# Version2.net
KiCad netlist of a schematic drawn in EasyEDA Pro
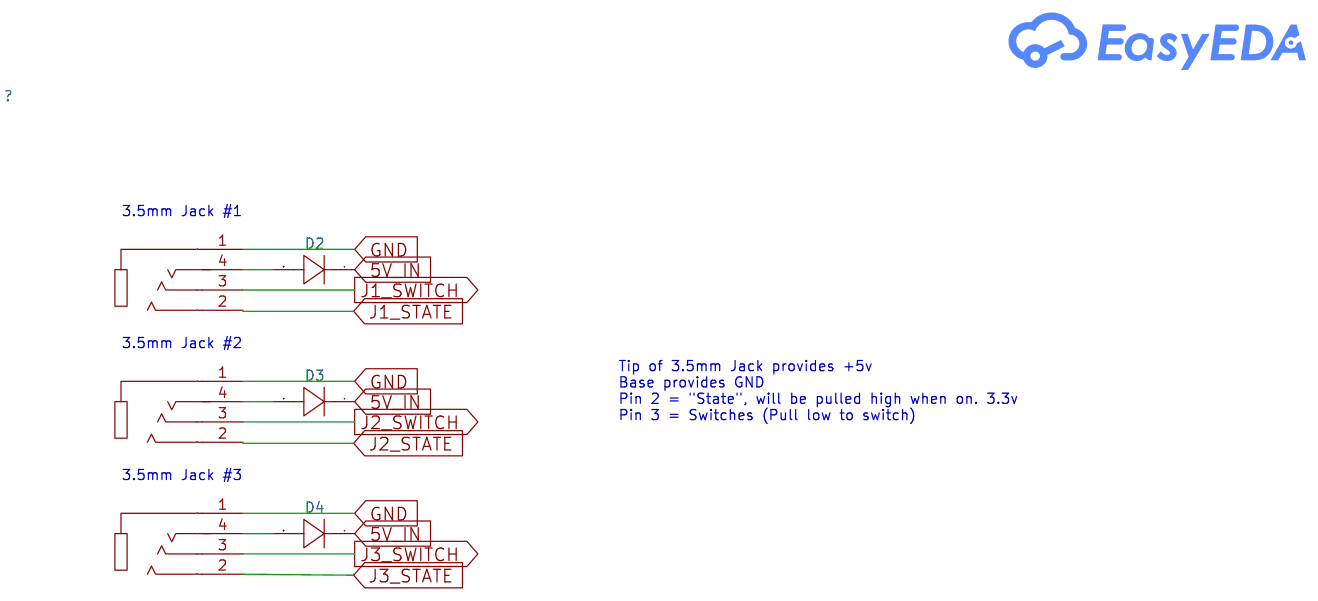
[diagram p0: inputs]
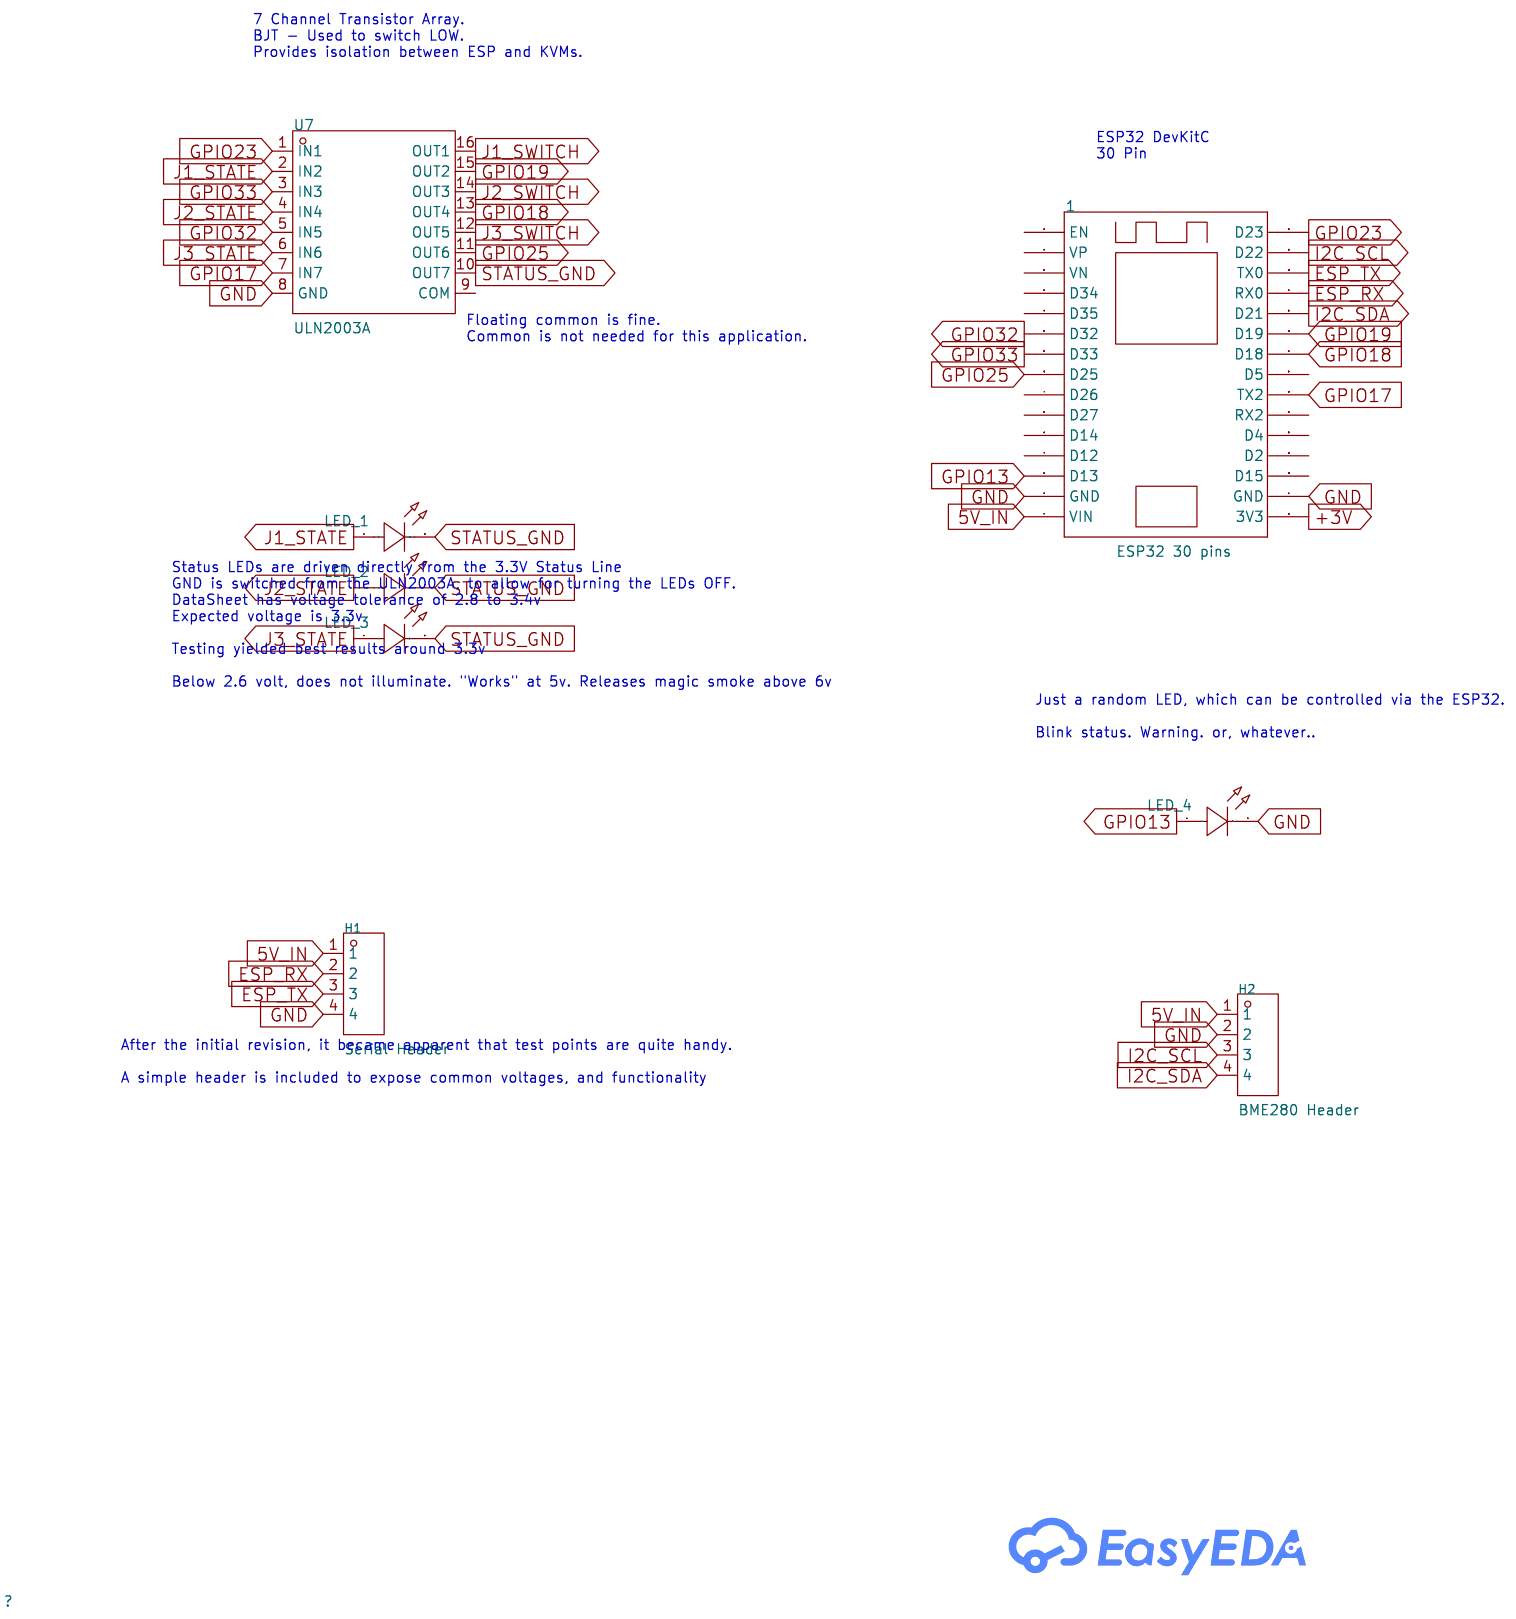
[diagram p1: logic]

(export (version "E")
  (design (tool "Eeschema 10.0.6"))
  (components
    (comp (ref "3.5mm1")
      (value "PJ-320D")
      (footprint "easyedapro:AUDIO-SMD_PJ-320D")
      (fields (field (name "Manufacturer") "SHOU HAN(首韩)"))
      (libsource (lib "easyedapro") (part "PJ-320D"))
    )
    (comp (ref "3.5mm2")
      (value "PJ-320D")
      (footprint "easyedapro:AUDIO-SMD_PJ-320D")
      (fields (field (name "Manufacturer") "SHOU HAN(首韩)"))
      (libsource (lib "easyedapro") (part "PJ-320D"))
    )
    (comp (ref "3.5mm3")
      (value "PJ-320D")
      (footprint "easyedapro:AUDIO-SMD_PJ-320D")
      (fields (field (name "Manufacturer") "SHOU HAN(首韩)"))
      (libsource (lib "easyedapro") (part "PJ-320D"))
    )
    (comp (ref "D2")
      (value "~")
      (footprint "easyedapro:DO-41_BD2.4-L4.7-P8.70-D0.9-RD")
      (libsource (lib "easyedapro") (part "D_1N4007"))
    )
    (comp (ref "D3")
      (value "~")
      (footprint "easyedapro:DO-41_BD2.4-L4.7-P8.70-D0.9-RD")
      (libsource (lib "easyedapro") (part "D_1N4007"))
    )
    (comp (ref "D4")
      (value "~")
      (footprint "easyedapro:DO-41_BD2.4-L4.7-P8.70-D0.9-RD")
      (libsource (lib "easyedapro") (part "D_1N4007"))
    )
    (comp (ref "1") (value "ESP32 30 pins") (libsource (lib "easyedapro") (part "ESP32 30 pins")))
    (comp (ref "H1")
      (value "Serial Header")
      (footprint "easyedapro:HDR-TH_4P-P2.54-V-M")
      (fields (field (name "Manufacturer") "XFCN(兴飞)"))
      (libsource (lib "easyedapro") (part "PZ254V-11-04P_C2691448"))
    )
    (comp (ref "H2")
      (value "BME280 Header")
      (footprint "easyedapro:HDR-TH_4P-P2.54-V-M")
      (fields (field (name "Manufacturer") "XFCN(兴飞)"))
      (libsource (lib "easyedapro") (part "PZ254V-11-04P_C2691448"))
    )
    (comp (ref "LED_1")
      (value "DY-332SUGD-A3")
      (footprint "easyedapro:LED-TH_BD5.9-P2.54-FD")
      (fields (field (name "Manufacturer") "TONYU(东裕)"))
      (libsource (lib "easyedapro") (part "DY-332SUGD-A3"))
    )
    (comp (ref "LED_2")
      (value "DY-332SUGD-A3")
      (footprint "easyedapro:LED-TH_BD5.9-P2.54-FD")
      (fields (field (name "Manufacturer") "TONYU(东裕)"))
      (libsource (lib "easyedapro") (part "DY-332SUGD-A3"))
    )
    (comp (ref "LED_3")
      (value "DY-332SUGD-A3")
      (footprint "easyedapro:LED-TH_BD5.9-P2.54-FD")
      (fields (field (name "Manufacturer") "TONYU(东裕)"))
      (libsource (lib "easyedapro") (part "DY-332SUGD-A3"))
    )
    (comp (ref "LED_4")
      (value "DY-332SUGD-A3")
      (footprint "easyedapro:LED-TH_BD5.9-P2.54-FD")
      (fields (field (name "Manufacturer") "TONYU(东裕)"))
      (libsource (lib "easyedapro") (part "DY-332SUGD-A3"))
    )
    (comp (ref "U7")
      (value "ULN2003A")
      (footprint "easyedapro:DIP-16_L20.0-W6.4-P2.54-LS7.6-BL")
      (fields (field (name "Manufacturer") "ST(意法半导体)"))
      (libsource (lib "easyedapro") (part "ULN2003A_C93000"))
    )
  )
  (nets
    (net (code "1") (name "+3V") (class "Default")
      (node (ref "1") (pin "16") (pinfunction "3V3_16") (pintype "bidirectional"))
    )
    (net (code "2") (name "5V_IN") (class "Default")
      (node (ref "1") (pin "1") (pinfunction "VIN_1") (pintype "bidirectional"))
      (node (ref "D2") (pin "1") (pinfunction "K_1") (pintype "input"))
      (node (ref "D3") (pin "1") (pinfunction "K_1") (pintype "input"))
      (node (ref "D4") (pin "1") (pinfunction "K_1") (pintype "input"))
      (node (ref "H1") (pin "1") (pinfunction "1_1") (pintype "input"))
      (node (ref "H2") (pin "1") (pinfunction "1_1") (pintype "input"))
    )
    (net (code "3") (name "ESP_RX") (class "Default")
      (node (ref "1") (pin "27") (pinfunction "RX0_27") (pintype "bidirectional"))
      (node (ref "H1") (pin "2") (pinfunction "2_2") (pintype "input"))
    )
    (net (code "4") (name "ESP_TX") (class "Default")
      (node (ref "1") (pin "28") (pinfunction "TX0_28") (pintype "bidirectional"))
      (node (ref "H1") (pin "3") (pinfunction "3_3") (pintype "input"))
    )
    (net (code "5") (name "GND") (class "Default")
      (node (ref "1") (pin "17") (pinfunction "GND_17") (pintype "bidirectional"))
      (node (ref "1") (pin "2") (pinfunction "GND_2") (pintype "bidirectional"))
      (node (ref "3.5mm1") (pin "1") (pinfunction "1_1") (pintype "unspecified"))
      (node (ref "3.5mm2") (pin "1") (pinfunction "1_1") (pintype "unspecified"))
      (node (ref "3.5mm3") (pin "1") (pinfunction "1_1") (pintype "unspecified"))
      (node (ref "H1") (pin "4") (pinfunction "4_4") (pintype "input"))
      (node (ref "H2") (pin "2") (pinfunction "2_2") (pintype "input"))
      (node (ref "LED_4") (pin "2") (pinfunction "C_2") (pintype "unspecified"))
      (node (ref "U7") (pin "8") (pinfunction "GND_8") (pintype "unspecified"))
    )
    (net (code "6") (name "GPIO13") (class "Default")
      (node (ref "1") (pin "3") (pinfunction "D13_3") (pintype "bidirectional"))
      (node (ref "LED_4") (pin "1") (pinfunction "A_1") (pintype "unspecified"))
    )
    (net (code "7") (name "GPIO17") (class "Default")
      (node (ref "1") (pin "22") (pinfunction "TX2_22") (pintype "bidirectional"))
      (node (ref "U7") (pin "7") (pinfunction "IN7_7") (pintype "unspecified"))
    )
    (net (code "8") (name "GPIO18") (class "Default")
      (node (ref "1") (pin "24") (pinfunction "D18_24") (pintype "bidirectional"))
      (node (ref "U7") (pin "13") (pinfunction "OUT4_13") (pintype "unspecified"))
    )
    (net (code "9") (name "GPIO19") (class "Default")
      (node (ref "1") (pin "25") (pinfunction "D19_25") (pintype "bidirectional"))
      (node (ref "U7") (pin "15") (pinfunction "OUT2_15") (pintype "unspecified"))
    )
    (net (code "10") (name "GPIO23") (class "Default")
      (node (ref "1") (pin "30") (pinfunction "D23_30") (pintype "bidirectional"))
      (node (ref "U7") (pin "1") (pinfunction "IN1_1") (pintype "unspecified"))
    )
    (net (code "11") (name "GPIO25") (class "Default")
      (node (ref "1") (pin "8") (pinfunction "D25_8") (pintype "bidirectional"))
      (node (ref "U7") (pin "11") (pinfunction "OUT6_11") (pintype "unspecified"))
    )
    (net (code "12") (name "GPIO32") (class "Default")
      (node (ref "1") (pin "10") (pinfunction "D32_10") (pintype "bidirectional"))
      (node (ref "U7") (pin "5") (pinfunction "IN5_5") (pintype "unspecified"))
    )
    (net (code "13") (name "GPIO33") (class "Default")
      (node (ref "1") (pin "9") (pinfunction "D33_9") (pintype "bidirectional"))
      (node (ref "U7") (pin "3") (pinfunction "IN3_3") (pintype "unspecified"))
    )
    (net (code "14") (name "I2C_SCL") (class "Default")
      (node (ref "1") (pin "29") (pinfunction "D22_29") (pintype "bidirectional"))
      (node (ref "H2") (pin "3") (pinfunction "3_3") (pintype "input"))
    )
    (net (code "15") (name "I2C_SDA") (class "Default")
      (node (ref "1") (pin "26") (pinfunction "D21_26") (pintype "bidirectional"))
      (node (ref "H2") (pin "4") (pinfunction "4_4") (pintype "input"))
    )
    (net (code "16") (name "J1_STATE") (class "Default")
      (node (ref "3.5mm1") (pin "2") (pinfunction "2_2") (pintype "unspecified"))
      (node (ref "LED_1") (pin "1") (pinfunction "A_1") (pintype "unspecified"))
      (node (ref "U7") (pin "2") (pinfunction "IN2_2") (pintype "unspecified"))
    )
    (net (code "17") (name "J1_SWITCH") (class "Default")
      (node (ref "3.5mm1") (pin "3") (pinfunction "3_3") (pintype "unspecified"))
      (node (ref "U7") (pin "16") (pinfunction "OUT1_16") (pintype "unspecified"))
    )
    (net (code "18") (name "J2_STATE") (class "Default")
      (node (ref "3.5mm2") (pin "2") (pinfunction "2_2") (pintype "unspecified"))
      (node (ref "LED_2") (pin "1") (pinfunction "A_1") (pintype "unspecified"))
      (node (ref "U7") (pin "4") (pinfunction "IN4_4") (pintype "unspecified"))
    )
    (net (code "19") (name "J2_SWITCH") (class "Default")
      (node (ref "3.5mm2") (pin "3") (pinfunction "3_3") (pintype "unspecified"))
      (node (ref "U7") (pin "14") (pinfunction "OUT3_14") (pintype "unspecified"))
    )
    (net (code "20") (name "J3_STATE") (class "Default")
      (node (ref "3.5mm3") (pin "2") (pinfunction "2_2") (pintype "unspecified"))
      (node (ref "LED_3") (pin "1") (pinfunction "A_1") (pintype "unspecified"))
      (node (ref "U7") (pin "6") (pinfunction "IN6_6") (pintype "unspecified"))
    )
    (net (code "21") (name "J3_SWITCH") (class "Default")
      (node (ref "3.5mm3") (pin "3") (pinfunction "3_3") (pintype "unspecified"))
      (node (ref "U7") (pin "12") (pinfunction "OUT5_12") (pintype "unspecified"))
    )
    (net (code "22") (name "Net-(D2-A)") (class "Default")
      (node (ref "3.5mm1") (pin "4") (pinfunction "4_4") (pintype "unspecified"))
      (node (ref "D2") (pin "2") (pinfunction "A_2") (pintype "input"))
    )
    (net (code "23") (name "Net-(D3-A)") (class "Default")
      (node (ref "3.5mm2") (pin "4") (pinfunction "4_4") (pintype "unspecified"))
      (node (ref "D3") (pin "2") (pinfunction "A_2") (pintype "input"))
    )
    (net (code "24") (name "Net-(D4-A)") (class "Default")
      (node (ref "3.5mm3") (pin "4") (pinfunction "4_4") (pintype "unspecified"))
      (node (ref "D4") (pin "2") (pinfunction "A_2") (pintype "input"))
    )
    (net (code "25") (name "STATUS_GND") (class "Default")
      (node (ref "LED_1") (pin "2") (pinfunction "C_2") (pintype "unspecified"))
      (node (ref "LED_2") (pin "2") (pinfunction "C_2") (pintype "unspecified"))
      (node (ref "LED_3") (pin "2") (pinfunction "C_2") (pintype "unspecified"))
      (node (ref "U7") (pin "10") (pinfunction "OUT7_10") (pintype "unspecified"))
    )
    (net (code "26") (name "unconnected-(1-D2-Pad19)") (class "Default")
      (node (ref "1") (pin "19") (pinfunction "D2_19") (pintype "bidirectional"))
    )
    (net (code "27") (name "unconnected-(1-D4-Pad20)") (class "Default")
      (node (ref "1") (pin "20") (pinfunction "D4_20") (pintype "bidirectional"))
    )
    (net (code "28") (name "unconnected-(1-D5-Pad23)") (class "Default")
      (node (ref "1") (pin "23") (pinfunction "D5_23") (pintype "bidirectional"))
    )
    (net (code "29") (name "unconnected-(1-D12-Pad4)") (class "Default")
      (node (ref "1") (pin "4") (pinfunction "D12_4") (pintype "bidirectional"))
    )
    (net (code "30") (name "unconnected-(1-D14-Pad5)") (class "Default")
      (node (ref "1") (pin "5") (pinfunction "D14_5") (pintype "bidirectional"))
    )
    (net (code "31") (name "unconnected-(1-D15-Pad18)") (class "Default")
      (node (ref "1") (pin "18") (pinfunction "D15_18") (pintype "bidirectional"))
    )
    (net (code "32") (name "unconnected-(1-D26-Pad7)") (class "Default")
      (node (ref "1") (pin "7") (pinfunction "D26_7") (pintype "bidirectional"))
    )
    (net (code "33") (name "unconnected-(1-D27-Pad6)") (class "Default")
      (node (ref "1") (pin "6") (pinfunction "D27_6") (pintype "bidirectional"))
    )
    (net (code "34") (name "unconnected-(1-D34-Pad12)") (class "Default")
      (node (ref "1") (pin "12") (pinfunction "D34_12") (pintype "bidirectional"))
    )
    (net (code "35") (name "unconnected-(1-D35-Pad11)") (class "Default")
      (node (ref "1") (pin "11") (pinfunction "D35_11") (pintype "bidirectional"))
    )
    (net (code "36") (name "unconnected-(1-EN-Pad15)") (class "Default")
      (node (ref "1") (pin "15") (pinfunction "EN_15") (pintype "bidirectional"))
    )
    (net (code "37") (name "unconnected-(1-RX2-Pad21)") (class "Default")
      (node (ref "1") (pin "21") (pinfunction "RX2_21") (pintype "bidirectional"))
    )
    (net (code "38") (name "unconnected-(1-VN-Pad13)") (class "Default")
      (node (ref "1") (pin "13") (pinfunction "VN_13") (pintype "bidirectional"))
    )
    (net (code "39") (name "unconnected-(1-VP-Pad14)") (class "Default")
      (node (ref "1") (pin "14") (pinfunction "VP_14") (pintype "bidirectional"))
    )
    (net (code "40") (name "unconnected-(U7-COM-Pad9)") (class "Default")
      (node (ref "U7") (pin "9") (pinfunction "COM_9") (pintype "unspecified"))
    )
  )
)
